# SCH_Watch_Design_v1_2022-04-19.net
KiCad netlist of a schematic drawn in EasyEDA
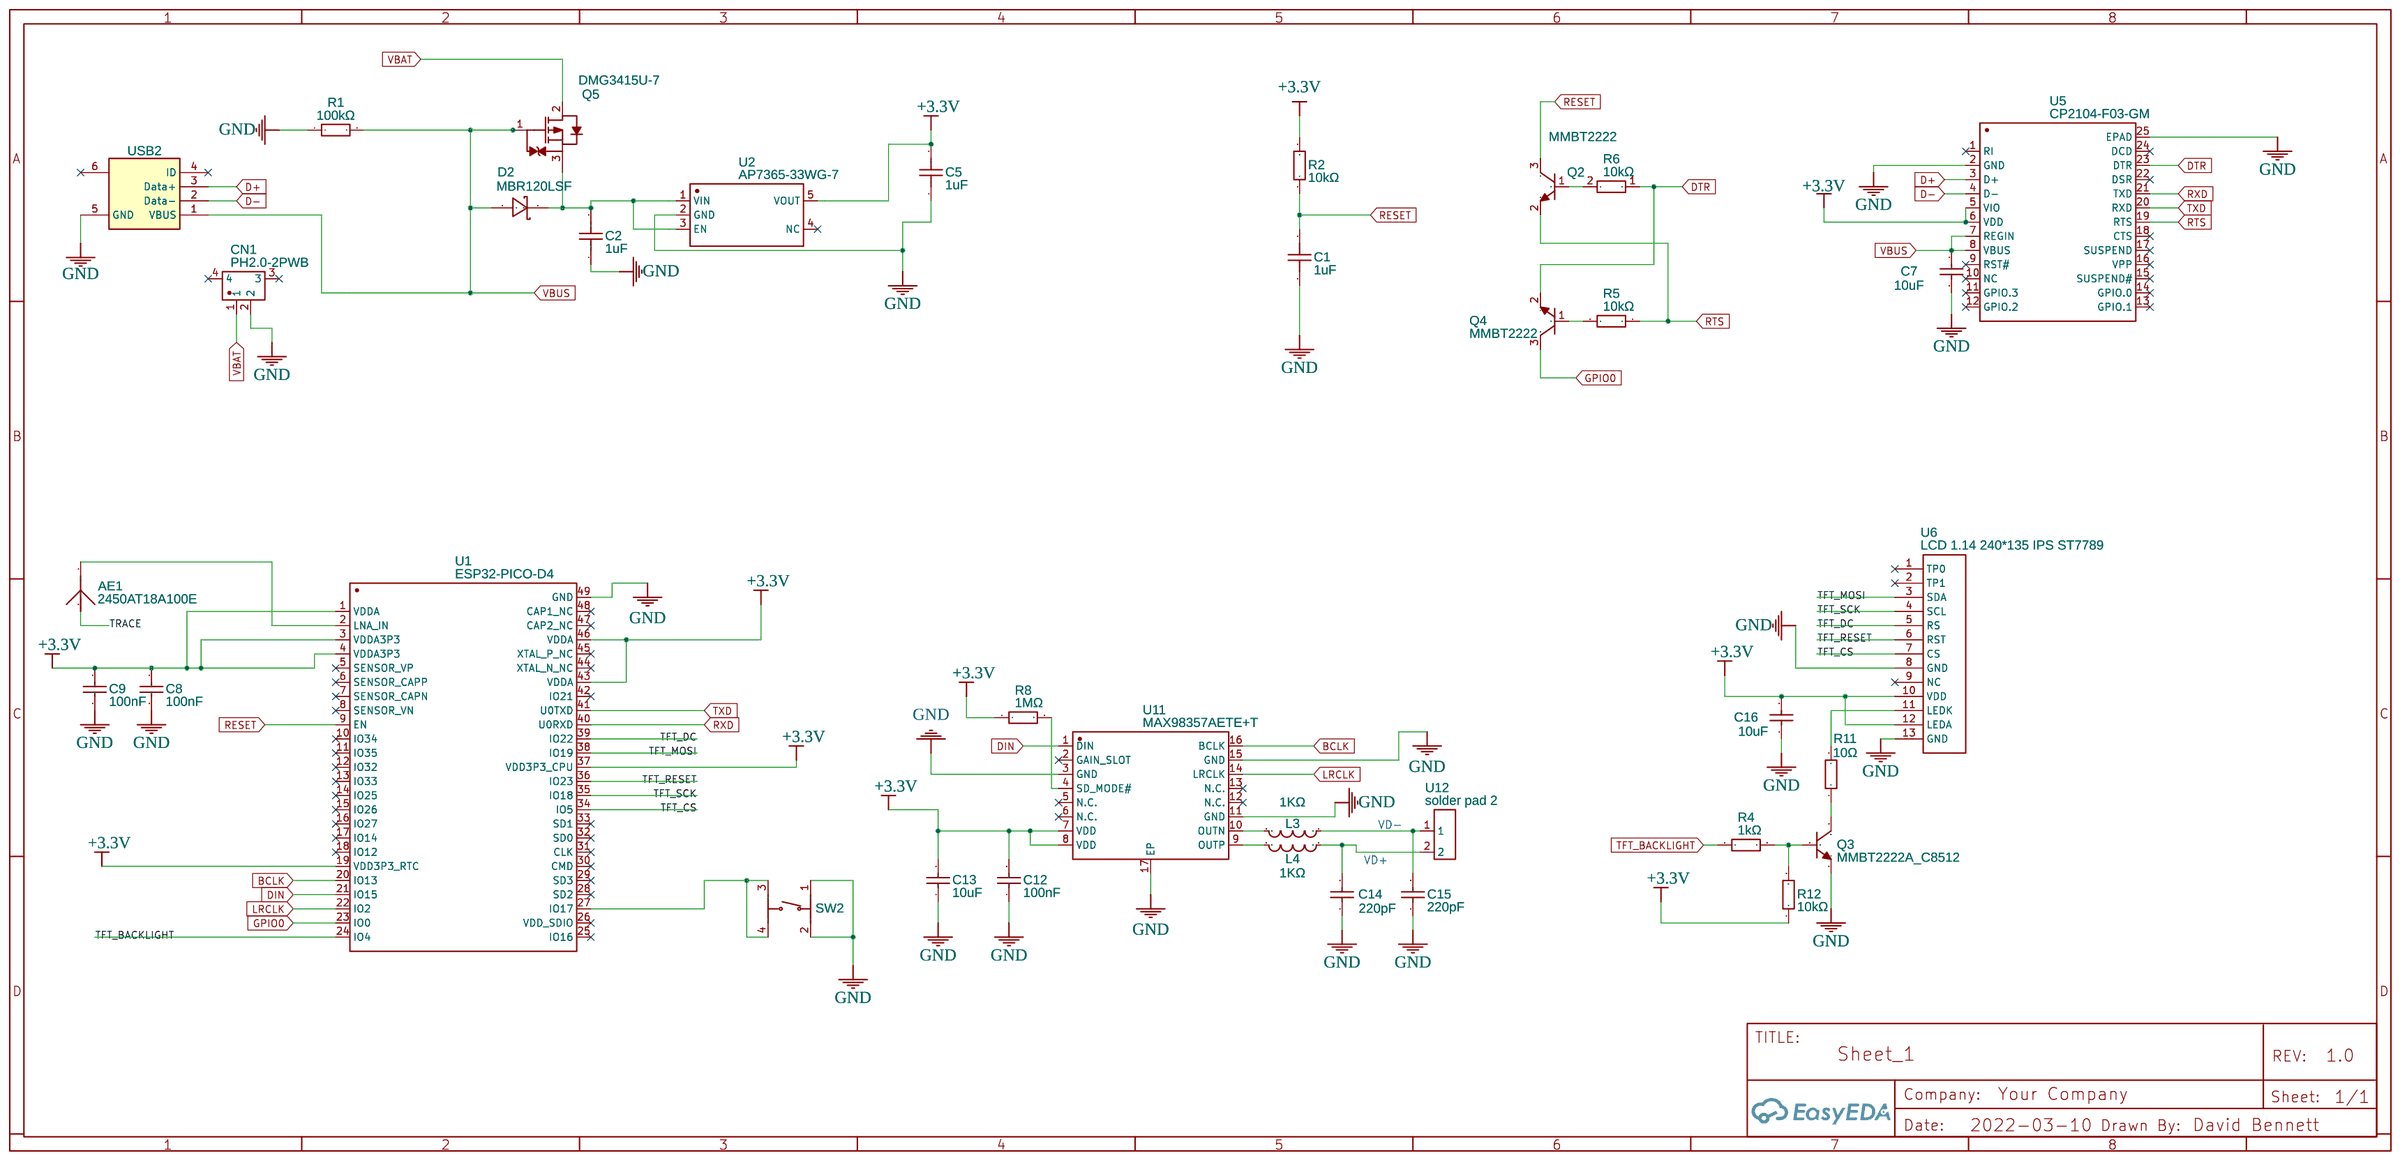
[diagram p0: schematic sheet]

(export (version "E")
  (design (tool "Eeschema 10.0.6"))
  (components
    (comp (ref "AE1")
      (value "2450AT18A100E")
      (fields (field (name "BOM_Supplier Part") "C89334"))
      (libsource (lib "") (part "2450AT18A100E"))
    )
    (comp (ref "C1")
      (value "1uF")
      (fields
        (field (name "BOM_Manufacturer Part") "CS1608X7R105K250NRB")
        (field (name "BOM_Supplier Part") "C513775")
      )
      (libsource (lib "") (part "CS1608X7R105K250NRB"))
    )
    (comp (ref "C2")
      (value "1uF")
      (fields
        (field (name "BOM_Manufacturer Part") "0402F105M6R3CT")
        (field (name "BOM_Supplier Part") "C408910")
      )
      (libsource (lib "") (part "0402F105M6R3CT"))
    )
    (comp (ref "C5")
      (value "1uF")
      (fields
        (field (name "BOM_Manufacturer Part") "0402F105M6R3CT")
        (field (name "BOM_Supplier Part") "C408910")
      )
      (libsource (lib "") (part "0402F105M6R3CT"))
    )
    (comp (ref "C7")
      (value "10uF")
      (fields
        (field (name "BOM_Manufacturer Part") "CL05A106MQ5NUNC")
        (field (name "BOM_Supplier Part") "C15525")
      )
      (libsource (lib "") (part "CL05A106MQ5NUNC"))
    )
    (comp (ref "C8")
      (value "100nF")
      (fields
        (field (name "BOM_Manufacturer Part") "0402F104M500NT")
        (field (name "BOM_Supplier Part") "C1581")
      )
      (libsource (lib "") (part "0402F104M500NT"))
    )
    (comp (ref "C9")
      (value "100nF")
      (fields
        (field (name "BOM_Manufacturer Part") "0402F104M500NT")
        (field (name "BOM_Supplier Part") "C1581")
      )
      (libsource (lib "") (part "0402F104M500NT"))
    )
    (comp (ref "C12")
      (value "100nF")
      (fields
        (field (name "BOM_Manufacturer Part") "0402F104M500NT")
        (field (name "BOM_Supplier Part") "C1581")
      )
      (libsource (lib "") (part "0402F104M500NT"))
    )
    (comp (ref "C13")
      (value "10uF")
      (fields
        (field (name "BOM_Manufacturer Part") "CL05A106MQ5NUNC")
        (field (name "BOM_Supplier Part") "C15525")
      )
      (libsource (lib "") (part "CL05A106MQ5NUNC"))
    )
    (comp (ref "C14")
      (value "220pF")
      (fields
        (field (name "BOM_Manufacturer Part") "0402B221K500NT")
        (field (name "BOM_Supplier Part") "C1530")
      )
      (libsource (lib "") (part "0402B221K500NT"))
    )
    (comp (ref "C15")
      (value "220pF")
      (fields
        (field (name "BOM_Manufacturer Part") "0402B221K500NT")
        (field (name "BOM_Supplier Part") "C1530")
      )
      (libsource (lib "") (part "0402B221K500NT"))
    )
    (comp (ref "C16")
      (value "10uF")
      (fields
        (field (name "BOM_Manufacturer Part") "CL05A106MQ5NUNC")
        (field (name "BOM_Supplier Part") "C15525")
      )
      (libsource (lib "") (part "CL05A106MQ5NUNC"))
    )
    (comp (ref "CN1")
      (value "PH2.0-2PWB")
      (fields
        (field (name "BOM_Manufacturer Part") "PH2.0-2PWB Horizontal")
        (field (name "BOM_Supplier Part") "C47647")
      )
      (libsource (lib "") (part "PH2.0-2PWB"))
    )
    (comp (ref "D2")
      (value "MBR120LSF")
      (fields (field (name "BOM_Supplier Part") "C130880"))
      (libsource (lib "") (part "MBR120LSF"))
    )
    (comp (ref "L3")
      (value "1KΩ")
      (fields
        (field (name "BOM_Manufacturer Part") "BLM18AG102SN1D")
        (field (name "BOM_Supplier Part") "C85824")
      )
      (libsource (lib "") (part "BLM18AG102SN1D"))
    )
    (comp (ref "L4")
      (value "1KΩ")
      (fields
        (field (name "BOM_Manufacturer Part") "BLM18AG102SN1D")
        (field (name "BOM_Supplier Part") "C85824")
      )
      (libsource (lib "") (part "BLM18AG102SN1D"))
    )
    (comp (ref "Q2")
      (value "MMBT2222")
      (fields (field (name "BOM_Supplier Part") "C2891810"))
      (libsource (lib "") (part "MMBT2222"))
    )
    (comp (ref "Q3")
      (value "MMBT2222A_C8512")
      (fields (field (name "BOM_Manufacturer Part") "MMBT2222A") (field (name "BOM_Supplier Part") "C8512"))
      (libsource (lib "") (part "MMBT2222A_C8512"))
    )
    (comp (ref "Q4")
      (value "MMBT2222")
      (fields (field (name "BOM_Supplier Part") "C2891810"))
      (libsource (lib "") (part "MMBT2222_1"))
    )
    (comp (ref "Q5")
      (value "DMG3415U-7")
      (fields (field (name "BOM_Supplier Part") "C96616"))
      (libsource (lib "") (part "DMG3415U-7"))
    )
    (comp (ref "R1")
      (value "100kΩ")
      (fields
        (field (name "BOM_Manufacturer Part") "0402WGF1003TCE")
        (field (name "BOM_Supplier Part") "C25741")
      )
      (libsource (lib "") (part "0402WGF1003TCE"))
    )
    (comp (ref "R2")
      (value "10kΩ")
      (fields
        (field (name "BOM_Manufacturer Part") "0402WGF1002TCE")
        (field (name "BOM_Supplier Part") "C25744")
      )
      (libsource (lib "") (part "0402WGF1002TCE"))
    )
    (comp (ref "R4")
      (value "1kΩ")
      (fields
        (field (name "BOM_Manufacturer Part") "0402WGF1001TCE")
        (field (name "BOM_Supplier Part") "C11702")
      )
      (libsource (lib "") (part "0402WGF1001TCE"))
    )
    (comp (ref "R5")
      (value "10kΩ")
      (fields
        (field (name "BOM_Manufacturer Part") "0402WGF1002TCE")
        (field (name "BOM_Supplier Part") "C25744")
      )
      (libsource (lib "") (part "0402WGF1002TCE_1"))
    )
    (comp (ref "R6")
      (value "10kΩ")
      (fields
        (field (name "BOM_Manufacturer Part") "0402WGF1002TCE")
        (field (name "BOM_Supplier Part") "C25744")
      )
      (libsource (lib "") (part "0402WGF1002TCE_1"))
    )
    (comp (ref "R8")
      (value "1MΩ")
      (fields
        (field (name "BOM_Manufacturer Part") "0402WGF1004TCE")
        (field (name "BOM_Supplier Part") "C26083")
      )
      (libsource (lib "") (part "0402WGF1004TCE"))
    )
    (comp (ref "R11")
      (value "10Ω")
      (fields
        (field (name "BOM_Manufacturer Part") "0402WGF100JTCE")
        (field (name "BOM_Supplier Part") "C25077")
      )
      (libsource (lib "") (part "0402WGF100JTCE"))
    )
    (comp (ref "R12")
      (value "10kΩ")
      (fields
        (field (name "BOM_Manufacturer Part") "0402WGF1002TCE")
        (field (name "BOM_Supplier Part") "C25744")
      )
      (libsource (lib "") (part "0402WGF1002TCE"))
    )
    (comp (ref "SW2")
      (value "TS-1187A-B-A-B")
      (fields (field (name "BOM_Supplier Part") "C318884"))
      (libsource (lib "") (part "TS-1187A-B-A-B"))
    )
    (comp (ref "U1")
      (value "ESP32-PICO-D4")
      (fields (field (name "BOM_Supplier Part") "C193707"))
      (libsource (lib "") (part "ESP32-PICO-D4"))
    )
    (comp (ref "U2")
      (value "AP7365-33WG-7")
      (fields (field (name "BOM_Supplier Part") "C150742"))
      (libsource (lib "") (part "AP7365-33WG-7"))
    )
    (comp (ref "U5")
      (value "CP2104-F03-GM")
      (fields (field (name "BOM_Supplier Part") "C47742"))
      (libsource (lib "") (part "CP2104-F03-GM"))
    )
    (comp (ref "U6")
      (value "LCD 1.14 240*135 IPS ST7789")
      (fields (field (name "BOM_Manufacturer Part") "IPS 160x80 ST7735"))
      (libsource (lib "") (part "LCD 1.14 240*135 IPS ST7789"))
    )
    (comp (ref "U11")
      (value "MAX98357AETE+T")
      (fields (field (name "BOM_Supplier Part") "C910544"))
      (libsource (lib "") (part "MAX98357AETE+T"))
    )
    (comp (ref "U12")
      (value "solder pad 2")
      (fields (field (name "BOM_Manufacturer Part") "Solder Pads"))
      (libsource (lib "") (part "solder pad 2"))
    )
    (comp (ref "USB2")
      (value "47346-0001")
      (fields (field (name "BOM_Supplier Part") "C132560"))
      (libsource (lib "") (part "47346-0001"))
    )
  )
  (nets
    (net (code "1") (name "+3.3V") (class "Default")
      (node (ref "C12") (pin "2") (pinfunction "2_2") (pintype "input"))
      (node (ref "C13") (pin "2") (pinfunction "2_2") (pintype "input"))
      (node (ref "C16") (pin "2") (pinfunction "2_2") (pintype "input"))
      (node (ref "C5") (pin "2") (pinfunction "2_2") (pintype "unspecified"))
      (node (ref "C8") (pin "2") (pinfunction "2_2") (pintype "input"))
      (node (ref "C9") (pin "2") (pinfunction "2_2") (pintype "input"))
      (node (ref "R12") (pin "1") (pinfunction "1_1") (pintype "input"))
      (node (ref "R2") (pin "2") (pinfunction "2_2") (pintype "input"))
      (node (ref "R8") (pin "1") (pinfunction "1_1") (pintype "input"))
      (node (ref "U1") (pin "1") (pinfunction "VDDA_1") (pintype "unspecified"))
      (node (ref "U1") (pin "19") (pinfunction "VDD3P3_RTC_19") (pintype "unspecified"))
      (node (ref "U1") (pin "3") (pinfunction "VDDA3P3_3") (pintype "unspecified"))
      (node (ref "U1") (pin "37") (pinfunction "VDD3P3_CPU_37") (pintype "unspecified"))
      (node (ref "U1") (pin "4") (pinfunction "VDDA3P3_4") (pintype "unspecified"))
      (node (ref "U1") (pin "43") (pinfunction "VDDA_43") (pintype "unspecified"))
      (node (ref "U1") (pin "46") (pinfunction "VDDA_46") (pintype "unspecified"))
      (node (ref "U11") (pin "7") (pinfunction "VDD_7") (pintype "unspecified"))
      (node (ref "U11") (pin "8") (pinfunction "VDD_8") (pintype "unspecified"))
      (node (ref "U2") (pin "5") (pinfunction "VOUT_5") (pintype "unspecified"))
      (node (ref "U5") (pin "5") (pinfunction "VIO_5") (pintype "unspecified"))
      (node (ref "U5") (pin "6") (pinfunction "VDD_6") (pintype "unspecified"))
      (node (ref "U6") (pin "10") (pinfunction "VDD_10") (pintype "unspecified"))
      (node (ref "U6") (pin "12") (pinfunction "LEDA_12") (pintype "unspecified"))
    )
    (net (code "2") (name "/TFT_CS") (class "Default")
      (node (ref "U1") (pin "34") (pinfunction "IO5_34") (pintype "unspecified"))
      (node (ref "U6") (pin "7") (pinfunction "CS_7") (pintype "unspecified"))
    )
    (net (code "3") (name "/TFT_DC") (class "Default")
      (node (ref "U1") (pin "39") (pinfunction "IO22_39") (pintype "unspecified"))
      (node (ref "U6") (pin "5") (pinfunction "RS_5") (pintype "unspecified"))
    )
    (net (code "4") (name "/TFT_MOSI") (class "Default")
      (node (ref "U1") (pin "38") (pinfunction "IO19_38") (pintype "unspecified"))
      (node (ref "U6") (pin "3") (pinfunction "SDA_3") (pintype "unspecified"))
    )
    (net (code "5") (name "/TFT_RESET") (class "Default")
      (node (ref "U1") (pin "36") (pinfunction "IO23_36") (pintype "unspecified"))
      (node (ref "U6") (pin "6") (pinfunction "RST_6") (pintype "unspecified"))
    )
    (net (code "6") (name "/TFT_SCK") (class "Default")
      (node (ref "U1") (pin "35") (pinfunction "IO18_35") (pintype "unspecified"))
      (node (ref "U6") (pin "4") (pinfunction "SCL_4") (pintype "unspecified"))
    )
    (net (code "7") (name "/TRACE") (class "Default")
      (node (ref "AE1") (pin "2") (pinfunction "2_2") (pintype "unspecified"))
    )
    (net (code "8") (name "BCLK") (class "Default")
      (node (ref "U1") (pin "20") (pinfunction "IO13_20") (pintype "unspecified"))
      (node (ref "U11") (pin "16") (pinfunction "BCLK_16") (pintype "unspecified"))
    )
    (net (code "9") (name "D+") (class "Default")
      (node (ref "U5") (pin "3") (pinfunction "D+_3") (pintype "unspecified"))
      (node (ref "USB2") (pin "3") (pinfunction "Data+_3") (pintype "input"))
    )
    (net (code "10") (name "D-") (class "Default")
      (node (ref "U5") (pin "4") (pinfunction "D-_4") (pintype "unspecified"))
      (node (ref "USB2") (pin "2") (pinfunction "Data-_2") (pintype "input"))
    )
    (net (code "11") (name "DIN") (class "Default")
      (node (ref "U1") (pin "21") (pinfunction "IO15_21") (pintype "unspecified"))
      (node (ref "U11") (pin "1") (pinfunction "DIN_1") (pintype "unspecified"))
    )
    (net (code "12") (name "DTR") (class "Default")
      (node (ref "Q4") (pin "2") (pinfunction "E_2") (pintype "input"))
      (node (ref "R6") (pin "1") (pinfunction "1_1") (pintype "input"))
      (node (ref "U5") (pin "23") (pinfunction "DTR_23") (pintype "unspecified"))
    )
    (net (code "13") (name "GND") (class "Default")
      (node (ref "C1") (pin "1") (pinfunction "1_1") (pintype "unspecified"))
      (node (ref "C12") (pin "1") (pinfunction "1_1") (pintype "input"))
      (node (ref "C13") (pin "1") (pinfunction "1_1") (pintype "input"))
      (node (ref "C14") (pin "1") (pinfunction "1_1") (pintype "input"))
      (node (ref "C15") (pin "1") (pinfunction "1_1") (pintype "input"))
      (node (ref "C16") (pin "1") (pinfunction "1_1") (pintype "input"))
      (node (ref "C2") (pin "1") (pinfunction "1_1") (pintype "unspecified"))
      (node (ref "C5") (pin "1") (pinfunction "1_1") (pintype "unspecified"))
      (node (ref "C7") (pin "1") (pinfunction "1_1") (pintype "input"))
      (node (ref "C8") (pin "1") (pinfunction "1_1") (pintype "input"))
      (node (ref "C9") (pin "1") (pinfunction "1_1") (pintype "input"))
      (node (ref "CN1") (pin "2") (pinfunction "2_2") (pintype "unspecified"))
      (node (ref "Q3") (pin "2") (pinfunction "E_2") (pintype "unspecified"))
      (node (ref "R1") (pin "1") (pinfunction "1_1") (pintype "input"))
      (node (ref "SW2") (pin "1") (pinfunction "A_1") (pintype "unspecified"))
      (node (ref "SW2") (pin "2") (pinfunction "B_2") (pintype "unspecified"))
      (node (ref "U1") (pin "49") (pinfunction "GND_49") (pintype "unspecified"))
      (node (ref "U11") (pin "11") (pinfunction "GND_11") (pintype "unspecified"))
      (node (ref "U11") (pin "15") (pinfunction "GND_15") (pintype "unspecified"))
      (node (ref "U11") (pin "17") (pinfunction "EP_17") (pintype "unspecified"))
      (node (ref "U11") (pin "3") (pinfunction "GND_3") (pintype "unspecified"))
      (node (ref "U2") (pin "2") (pinfunction "GND_2") (pintype "unspecified"))
      (node (ref "U5") (pin "2") (pinfunction "GND_2") (pintype "unspecified"))
      (node (ref "U5") (pin "25") (pinfunction "EPAD_25") (pintype "unspecified"))
      (node (ref "U6") (pin "13") (pinfunction "GND_13") (pintype "unspecified"))
      (node (ref "U6") (pin "8") (pinfunction "GND_8") (pintype "unspecified"))
      (node (ref "USB2") (pin "5") (pinfunction "GND_5") (pintype "bidirectional"))
    )
    (net (code "14") (name "GPIO0") (class "Default")
      (node (ref "Q4") (pin "3") (pinfunction "C_3") (pintype "input"))
      (node (ref "U1") (pin "23") (pinfunction "IO0_23") (pintype "unspecified"))
    )
    (net (code "15") (name "LRCLK") (class "Default")
      (node (ref "U1") (pin "22") (pinfunction "IO2_22") (pintype "unspecified"))
      (node (ref "U11") (pin "14") (pinfunction "LRCLK_14") (pintype "unspecified"))
    )
    (net (code "16") (name "Net-(AE1-ANT)") (class "Default")
      (node (ref "AE1") (pin "1") (pinfunction "ANT_1") (pintype "unspecified"))
      (node (ref "U1") (pin "2") (pinfunction "LNA_IN_2") (pintype "unspecified"))
    )
    (net (code "17") (name "Net-(C14-Pad2)") (class "Default")
      (node (ref "C14") (pin "2") (pinfunction "2_2") (pintype "input"))
      (node (ref "L4") (pin "1") (pinfunction "1_1") (pintype "unspecified"))
      (node (ref "U12") (pin "2") (pinfunction "2_2") (pintype "unspecified"))
    )
    (net (code "18") (name "Net-(C15-Pad2)") (class "Default")
      (node (ref "C15") (pin "2") (pinfunction "2_2") (pintype "input"))
      (node (ref "L3") (pin "1") (pinfunction "1_1") (pintype "unspecified"))
      (node (ref "U12") (pin "1") (pinfunction "1_1") (pintype "unspecified"))
    )
    (net (code "19") (name "Net-(D2-C)") (class "Default")
      (node (ref "C2") (pin "2") (pinfunction "2_2") (pintype "unspecified"))
      (node (ref "D2") (pin "1") (pinfunction "C_1") (pintype "unspecified"))
      (node (ref "Q5") (pin "3") (pinfunction "S_3") (pintype "unspecified"))
      (node (ref "U2") (pin "1") (pinfunction "VIN_1") (pintype "unspecified"))
      (node (ref "U2") (pin "3") (pinfunction "EN_3") (pintype "unspecified"))
    )
    (net (code "20") (name "Net-(Q2-B)") (class "Default")
      (node (ref "Q2") (pin "1") (pinfunction "B_1") (pintype "input"))
      (node (ref "R6") (pin "2") (pinfunction "2_2") (pintype "input"))
    )
    (net (code "21") (name "Net-(Q3-B)") (class "Default")
      (node (ref "Q3") (pin "1") (pinfunction "B_1") (pintype "unspecified"))
      (node (ref "R12") (pin "2") (pinfunction "2_2") (pintype "input"))
      (node (ref "R4") (pin "2") (pinfunction "2_2") (pintype "input"))
    )
    (net (code "22") (name "Net-(Q3-C)") (class "Default")
      (node (ref "Q3") (pin "3") (pinfunction "C_3") (pintype "unspecified"))
      (node (ref "R11") (pin "1") (pinfunction "1_1") (pintype "input"))
    )
    (net (code "23") (name "Net-(Q4-B)") (class "Default")
      (node (ref "Q4") (pin "1") (pinfunction "B_1") (pintype "input"))
      (node (ref "R5") (pin "2") (pinfunction "2_2") (pintype "input"))
    )
    (net (code "24") (name "Net-(SW2-C)") (class "Default")
      (node (ref "SW2") (pin "3") (pinfunction "C_3") (pintype "unspecified"))
      (node (ref "SW2") (pin "4") (pinfunction "D_4") (pintype "unspecified"))
      (node (ref "U1") (pin "27") (pinfunction "IO17_27") (pintype "unspecified"))
    )
    (net (code "25") (name "Net-(U6-LEDK)") (class "Default")
      (node (ref "R11") (pin "2") (pinfunction "2_2") (pintype "input"))
      (node (ref "U6") (pin "11") (pinfunction "LEDK_11") (pintype "unspecified"))
    )
    (net (code "26") (name "Net-(U11-OUTN)") (class "Default")
      (node (ref "L3") (pin "2") (pinfunction "2_2") (pintype "unspecified"))
      (node (ref "U11") (pin "10") (pinfunction "OUTN_10") (pintype "unspecified"))
    )
    (net (code "27") (name "Net-(U11-OUTP)") (class "Default")
      (node (ref "L4") (pin "2") (pinfunction "2_2") (pintype "unspecified"))
      (node (ref "U11") (pin "9") (pinfunction "OUTP_9") (pintype "unspecified"))
    )
    (net (code "28") (name "Net-(U11-SD_MODE#)") (class "Default")
      (node (ref "R8") (pin "2") (pinfunction "2_2") (pintype "input"))
      (node (ref "U11") (pin "4") (pinfunction "SD_MODE#_4") (pintype "unspecified"))
    )
    (net (code "29") (name "RESET") (class "Default")
      (node (ref "C1") (pin "2") (pinfunction "2_2") (pintype "unspecified"))
      (node (ref "Q2") (pin "3") (pinfunction "C_3") (pintype "input"))
      (node (ref "R2") (pin "1") (pinfunction "1_1") (pintype "input"))
      (node (ref "U1") (pin "9") (pinfunction "EN_9") (pintype "unspecified"))
    )
    (net (code "30") (name "RTS") (class "Default")
      (node (ref "Q2") (pin "2") (pinfunction "E_2") (pintype "input"))
      (node (ref "R5") (pin "1") (pinfunction "1_1") (pintype "input"))
      (node (ref "U5") (pin "19") (pinfunction "RTS_19") (pintype "unspecified"))
    )
    (net (code "31") (name "RXD") (class "Default")
      (node (ref "U1") (pin "40") (pinfunction "U0RXD_40") (pintype "unspecified"))
      (node (ref "U5") (pin "21") (pinfunction "TXD_21") (pintype "unspecified"))
    )
    (net (code "32") (name "TFT_BACKLIGHT") (class "Default")
      (node (ref "R4") (pin "1") (pinfunction "1_1") (pintype "input"))
      (node (ref "U1") (pin "24") (pinfunction "IO4_24") (pintype "unspecified"))
    )
    (net (code "33") (name "TXD") (class "Default")
      (node (ref "U1") (pin "41") (pinfunction "U0TXD_41") (pintype "unspecified"))
      (node (ref "U5") (pin "20") (pinfunction "RXD_20") (pintype "unspecified"))
    )
    (net (code "34") (name "VBAT") (class "Default")
      (node (ref "CN1") (pin "1") (pinfunction "1_1") (pintype "unspecified"))
      (node (ref "Q5") (pin "2") (pinfunction "D_2") (pintype "unspecified"))
    )
    (net (code "35") (name "VBUS") (class "Default")
      (node (ref "C7") (pin "2") (pinfunction "2_2") (pintype "input"))
      (node (ref "D2") (pin "2") (pinfunction "A_2") (pintype "unspecified"))
      (node (ref "Q5") (pin "1") (pinfunction "G_1") (pintype "unspecified"))
      (node (ref "R1") (pin "2") (pinfunction "2_2") (pintype "input"))
      (node (ref "U5") (pin "7") (pinfunction "REGIN_7") (pintype "unspecified"))
      (node (ref "U5") (pin "8") (pinfunction "VBUS_8") (pintype "unspecified"))
      (node (ref "USB2") (pin "1") (pinfunction "VBUS_1") (pintype "bidirectional"))
    )
    (net (code "36") (name "unconnected-(CN1-Pad3)") (class "Default")
      (node (ref "CN1") (pin "3") (pinfunction "3_3") (pintype "unspecified+no_connect"))
    )
    (net (code "37") (name "unconnected-(CN1-Pad4)") (class "Default")
      (node (ref "CN1") (pin "4") (pinfunction "4_4") (pintype "unspecified+no_connect"))
    )
    (net (code "38") (name "unconnected-(U1-CAP1_NC-Pad48)") (class "Default")
      (node (ref "U1") (pin "48") (pinfunction "CAP1_NC_48") (pintype "unspecified+no_connect"))
    )
    (net (code "39") (name "unconnected-(U1-CAP2_NC-Pad47)") (class "Default")
      (node (ref "U1") (pin "47") (pinfunction "CAP2_NC_47") (pintype "unspecified+no_connect"))
    )
    (net (code "40") (name "unconnected-(U1-CLK-Pad31)") (class "Default")
      (node (ref "U1") (pin "31") (pinfunction "CLK_31") (pintype "unspecified+no_connect"))
    )
    (net (code "41") (name "unconnected-(U1-CMD-Pad30)") (class "Default")
      (node (ref "U1") (pin "30") (pinfunction "CMD_30") (pintype "unspecified+no_connect"))
    )
    (net (code "42") (name "unconnected-(U1-IO12-Pad18)") (class "Default")
      (node (ref "U1") (pin "18") (pinfunction "IO12_18") (pintype "unspecified+no_connect"))
    )
    (net (code "43") (name "unconnected-(U1-IO14-Pad17)") (class "Default")
      (node (ref "U1") (pin "17") (pinfunction "IO14_17") (pintype "unspecified+no_connect"))
    )
    (net (code "44") (name "unconnected-(U1-IO16-Pad25)") (class "Default")
      (node (ref "U1") (pin "25") (pinfunction "IO16_25") (pintype "unspecified+no_connect"))
    )
    (net (code "45") (name "unconnected-(U1-IO21-Pad42)") (class "Default")
      (node (ref "U1") (pin "42") (pinfunction "IO21_42") (pintype "unspecified+no_connect"))
    )
    (net (code "46") (name "unconnected-(U1-IO25-Pad14)") (class "Default")
      (node (ref "U1") (pin "14") (pinfunction "IO25_14") (pintype "unspecified+no_connect"))
    )
    (net (code "47") (name "unconnected-(U1-IO26-Pad15)") (class "Default")
      (node (ref "U1") (pin "15") (pinfunction "IO26_15") (pintype "unspecified+no_connect"))
    )
    (net (code "48") (name "unconnected-(U1-IO27-Pad16)") (class "Default")
      (node (ref "U1") (pin "16") (pinfunction "IO27_16") (pintype "unspecified+no_connect"))
    )
    (net (code "49") (name "unconnected-(U1-IO32-Pad12)") (class "Default")
      (node (ref "U1") (pin "12") (pinfunction "IO32_12") (pintype "unspecified+no_connect"))
    )
    (net (code "50") (name "unconnected-(U1-IO33-Pad13)") (class "Default")
      (node (ref "U1") (pin "13") (pinfunction "IO33_13") (pintype "unspecified+no_connect"))
    )
    (net (code "51") (name "unconnected-(U1-IO34-Pad10)") (class "Default")
      (node (ref "U1") (pin "10") (pinfunction "IO34_10") (pintype "unspecified+no_connect"))
    )
    (net (code "52") (name "unconnected-(U1-IO35-Pad11)") (class "Default")
      (node (ref "U1") (pin "11") (pinfunction "IO35_11") (pintype "unspecified+no_connect"))
    )
    (net (code "53") (name "unconnected-(U1-SD0-Pad32)") (class "Default")
      (node (ref "U1") (pin "32") (pinfunction "SD0_32") (pintype "unspecified+no_connect"))
    )
    (net (code "54") (name "unconnected-(U1-SD1-Pad33)") (class "Default")
      (node (ref "U1") (pin "33") (pinfunction "SD1_33") (pintype "unspecified+no_connect"))
    )
    (net (code "55") (name "unconnected-(U1-SD2-Pad28)") (class "Default")
      (node (ref "U1") (pin "28") (pinfunction "SD2_28") (pintype "unspecified+no_connect"))
    )
    (net (code "56") (name "unconnected-(U1-SD3-Pad29)") (class "Default")
      (node (ref "U1") (pin "29") (pinfunction "SD3_29") (pintype "unspecified+no_connect"))
    )
    (net (code "57") (name "unconnected-(U1-SENSOR_CAPN-Pad7)") (class "Default")
      (node (ref "U1") (pin "7") (pinfunction "SENSOR_CAPN_7") (pintype "unspecified+no_connect"))
    )
    (net (code "58") (name "unconnected-(U1-SENSOR_CAPP-Pad6)") (class "Default")
      (node (ref "U1") (pin "6") (pinfunction "SENSOR_CAPP_6") (pintype "unspecified+no_connect"))
    )
    (net (code "59") (name "unconnected-(U1-SENSOR_VN-Pad8)") (class "Default")
      (node (ref "U1") (pin "8") (pinfunction "SENSOR_VN_8") (pintype "unspecified+no_connect"))
    )
    (net (code "60") (name "unconnected-(U1-SENSOR_VP-Pad5)") (class "Default")
      (node (ref "U1") (pin "5") (pinfunction "SENSOR_VP_5") (pintype "unspecified+no_connect"))
    )
    (net (code "61") (name "unconnected-(U1-VDD_SDIO-Pad26)") (class "Default")
      (node (ref "U1") (pin "26") (pinfunction "VDD_SDIO_26") (pintype "unspecified+no_connect"))
    )
    (net (code "62") (name "unconnected-(U1-XTAL_N_NC-Pad44)") (class "Default")
      (node (ref "U1") (pin "44") (pinfunction "XTAL_N_NC_44") (pintype "unspecified+no_connect"))
    )
    (net (code "63") (name "unconnected-(U1-XTAL_P_NC-Pad45)") (class "Default")
      (node (ref "U1") (pin "45") (pinfunction "XTAL_P_NC_45") (pintype "unspecified+no_connect"))
    )
    (net (code "64") (name "unconnected-(U2-NC-Pad4)") (class "Default")
      (node (ref "U2") (pin "4") (pinfunction "NC_4") (pintype "unspecified+no_connect"))
    )
    (net (code "65") (name "unconnected-(U5-CTS-Pad18)") (class "Default")
      (node (ref "U5") (pin "18") (pinfunction "CTS_18") (pintype "unspecified+no_connect"))
    )
    (net (code "66") (name "unconnected-(U5-DCD-Pad24)") (class "Default")
      (node (ref "U5") (pin "24") (pinfunction "DCD_24") (pintype "unspecified+no_connect"))
    )
    (net (code "67") (name "unconnected-(U5-DSR-Pad22)") (class "Default")
      (node (ref "U5") (pin "22") (pinfunction "DSR_22") (pintype "unspecified+no_connect"))
    )
    (net (code "68") (name "unconnected-(U5-GPIO.0-Pad14)") (class "Default")
      (node (ref "U5") (pin "14") (pinfunction "GPIO.0_14") (pintype "unspecified+no_connect"))
    )
    (net (code "69") (name "unconnected-(U5-GPIO.1-Pad13)") (class "Default")
      (node (ref "U5") (pin "13") (pinfunction "GPIO.1_13") (pintype "unspecified+no_connect"))
    )
    (net (code "70") (name "unconnected-(U5-GPIO.2-Pad12)") (class "Default")
      (node (ref "U5") (pin "12") (pinfunction "GPIO.2_12") (pintype "unspecified+no_connect"))
    )
    (net (code "71") (name "unconnected-(U5-GPIO.3-Pad11)") (class "Default")
      (node (ref "U5") (pin "11") (pinfunction "GPIO.3_11") (pintype "unspecified+no_connect"))
    )
    (net (code "72") (name "unconnected-(U5-NC-Pad10)") (class "Default")
      (node (ref "U5") (pin "10") (pinfunction "NC_10") (pintype "unspecified+no_connect"))
    )
    (net (code "73") (name "unconnected-(U5-RI-Pad1)") (class "Default")
      (node (ref "U5") (pin "1") (pinfunction "RI_1") (pintype "unspecified+no_connect"))
    )
    (net (code "74") (name "unconnected-(U5-RST#-Pad9)") (class "Default")
      (node (ref "U5") (pin "9") (pinfunction "RST#_9") (pintype "unspecified+no_connect"))
    )
    (net (code "75") (name "unconnected-(U5-SUSPEND#-Pad15)") (class "Default")
      (node (ref "U5") (pin "15") (pinfunction "SUSPEND#_15") (pintype "unspecified+no_connect"))
    )
    (net (code "76") (name "unconnected-(U5-SUSPEND-Pad17)") (class "Default")
      (node (ref "U5") (pin "17") (pinfunction "SUSPEND_17") (pintype "unspecified+no_connect"))
    )
    (net (code "77") (name "unconnected-(U5-VPP-Pad16)") (class "Default")
      (node (ref "U5") (pin "16") (pinfunction "VPP_16") (pintype "unspecified+no_connect"))
    )
    (net (code "78") (name "unconnected-(U6-NC-Pad9)") (class "Default")
      (node (ref "U6") (pin "9") (pinfunction "NC_9") (pintype "unspecified+no_connect"))
    )
    (net (code "79") (name "unconnected-(U6-TP0-Pad1)") (class "Default")
      (node (ref "U6") (pin "1") (pinfunction "TP0_1") (pintype "unspecified+no_connect"))
    )
    (net (code "80") (name "unconnected-(U6-TP1-Pad2)") (class "Default")
      (node (ref "U6") (pin "2") (pinfunction "TP1_2") (pintype "unspecified+no_connect"))
    )
    (net (code "81") (name "unconnected-(U11-GAIN_SLOT-Pad2)") (class "Default")
      (node (ref "U11") (pin "2") (pinfunction "GAIN_SLOT_2") (pintype "unspecified+no_connect"))
    )
    (net (code "82") (name "unconnected-(U11-N.C.-Pad5)") (class "Default")
      (node (ref "U11") (pin "5") (pinfunction "N.C._5") (pintype "unspecified+no_connect"))
    )
    (net (code "83") (name "unconnected-(U11-N.C.-Pad6)") (class "Default")
      (node (ref "U11") (pin "6") (pinfunction "N.C._6") (pintype "unspecified+no_connect"))
    )
    (net (code "84") (name "unconnected-(U11-N.C.-Pad12)") (class "Default")
      (node (ref "U11") (pin "12") (pinfunction "N.C._12") (pintype "unspecified+no_connect"))
    )
    (net (code "85") (name "unconnected-(U11-N.C.-Pad13)") (class "Default")
      (node (ref "U11") (pin "13") (pinfunction "N.C._13") (pintype "unspecified+no_connect"))
    )
    (net (code "86") (name "unconnected-(USB2-ID-Pad4)") (class "Default")
      (node (ref "USB2") (pin "4") (pinfunction "ID_4") (pintype "bidirectional+no_connect"))
    )
    (net (code "87") (name "unconnected-(USB2-Pad6)") (class "Default")
      (node (ref "USB2") (pin "6") (pintype "unspecified+no_connect"))
    )
  )
)
